# Connections.net
KiCad netlist of a schematic drawn in Altium Designer
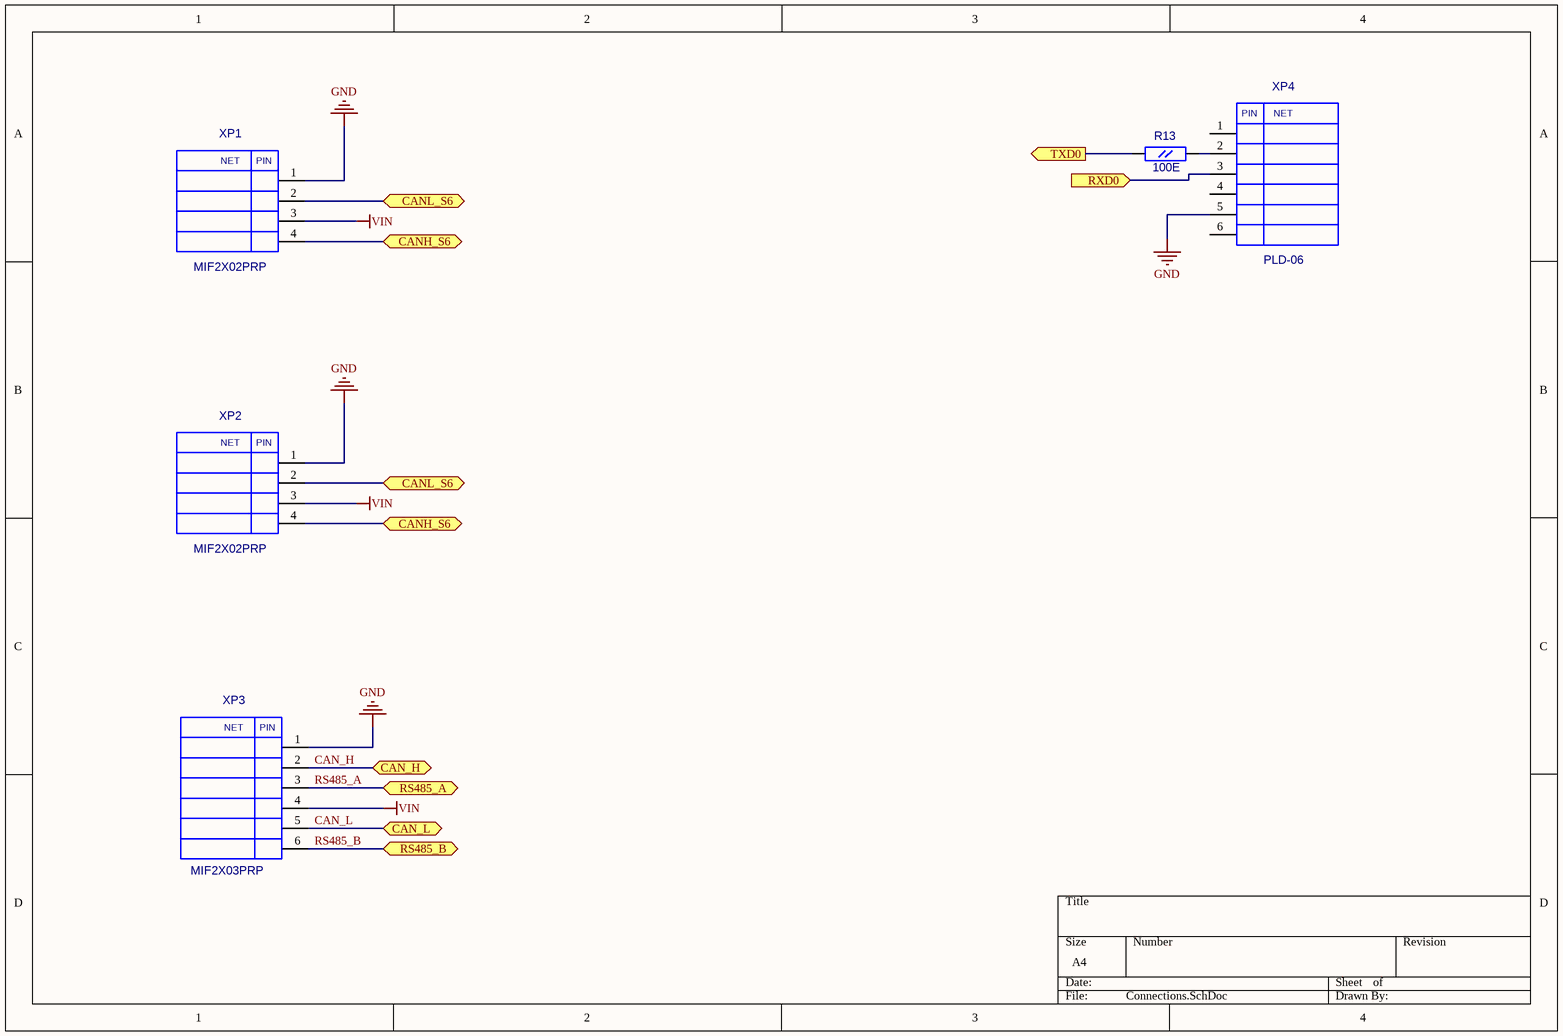
[diagram p0: Connections.SchDoc]

(export (version "E")
  (design (tool "Eeschema 10.0.6"))
  (components
    (comp (ref "R13")
      (value "100E")
      (footprint "RC0603")
      (description "RC0603")
      (libsource (lib "gprs_modem_2") (part "RC0603"))
    )
    (comp (ref "XP1")
      (value "MIF2X02PRP")
      (footprint "MIF2X02PRP")
      (libsource (lib "gprs_modem_2") (part "MIF2X02PRP"))
    )
    (comp (ref "XP2")
      (value "MIF2X02PRP")
      (footprint "MIF2X02PRP")
      (libsource (lib "gprs_modem_2") (part "MIF2X02PRP"))
    )
    (comp (ref "XP3")
      (value "MIF2X03PRP")
      (footprint "MIF2X03PRP")
      (libsource (lib "gprs_modem_2") (part "MIF2X03PRP"))
    )
    (comp (ref "XP4")
      (value "PLD-06")
      (footprint "PIN6")
      (description "PLD06")
      (libsource (lib "gprs_modem") (part "PLD-06"))
    )
  )
  (nets
    (net (code "1") (name "/CANH_S6") (class "Default")
      (node (ref "XP1") (pin "4") (pinfunction "4_4") (pintype "passive"))
      (node (ref "XP2") (pin "4") (pinfunction "4_4") (pintype "passive"))
    )
    (net (code "2") (name "/CANL_S6") (class "Default")
      (node (ref "XP1") (pin "2") (pinfunction "2_2") (pintype "passive"))
      (node (ref "XP2") (pin "2") (pinfunction "2_2") (pintype "passive"))
    )
    (net (code "3") (name "/CAN_H") (class "Default")
      (node (ref "XP3") (pin "2") (pinfunction "2_2") (pintype "passive"))
    )
    (net (code "4") (name "/CAN_L") (class "Default")
      (node (ref "XP3") (pin "5") (pinfunction "5_5") (pintype "passive"))
    )
    (net (code "5") (name "/RS485_A") (class "Default")
      (node (ref "XP3") (pin "3") (pinfunction "3_3") (pintype "passive"))
    )
    (net (code "6") (name "/RS485_B") (class "Default")
      (node (ref "XP3") (pin "6") (pinfunction "6_6") (pintype "passive"))
    )
    (net (code "7") (name "/RXD0") (class "Default")
      (node (ref "XP4") (pin "3") (pinfunction "3_3") (pintype "passive"))
    )
    (net (code "8") (name "/TXD0") (class "Default")
      (node (ref "R13") (pin "1") (pinfunction "A_1") (pintype "passive"))
    )
    (net (code "9") (name "GND") (class "Default")
      (node (ref "XP1") (pin "1") (pinfunction "1_1") (pintype "passive"))
      (node (ref "XP2") (pin "1") (pinfunction "1_1") (pintype "passive"))
      (node (ref "XP3") (pin "1") (pinfunction "1_1") (pintype "passive"))
      (node (ref "XP4") (pin "5") (pinfunction "5_5") (pintype "passive"))
    )
    (net (code "10") (name "Net-(R13-B)") (class "Default")
      (node (ref "R13") (pin "2") (pinfunction "B_2") (pintype "passive"))
      (node (ref "XP4") (pin "2") (pinfunction "2_2") (pintype "passive"))
    )
    (net (code "11") (name "VIN") (class "Default")
      (node (ref "XP1") (pin "3") (pinfunction "3_3") (pintype "passive"))
      (node (ref "XP2") (pin "3") (pinfunction "3_3") (pintype "passive"))
      (node (ref "XP3") (pin "4") (pinfunction "4_4") (pintype "passive"))
    )
    (net (code "12") (name "unconnected-(XP4-Pad1)") (class "Default")
      (node (ref "XP4") (pin "1") (pinfunction "1_1") (pintype "passive"))
    )
    (net (code "13") (name "unconnected-(XP4-Pad4)") (class "Default")
      (node (ref "XP4") (pin "4") (pinfunction "4_4") (pintype "passive"))
    )
    (net (code "14") (name "unconnected-(XP4-Pad6)") (class "Default")
      (node (ref "XP4") (pin "6") (pinfunction "6_6") (pintype "passive"))
    )
  )
)
